# Atari_2600_OD.net
KiCad netlist of a schematic drawn in EAGLE
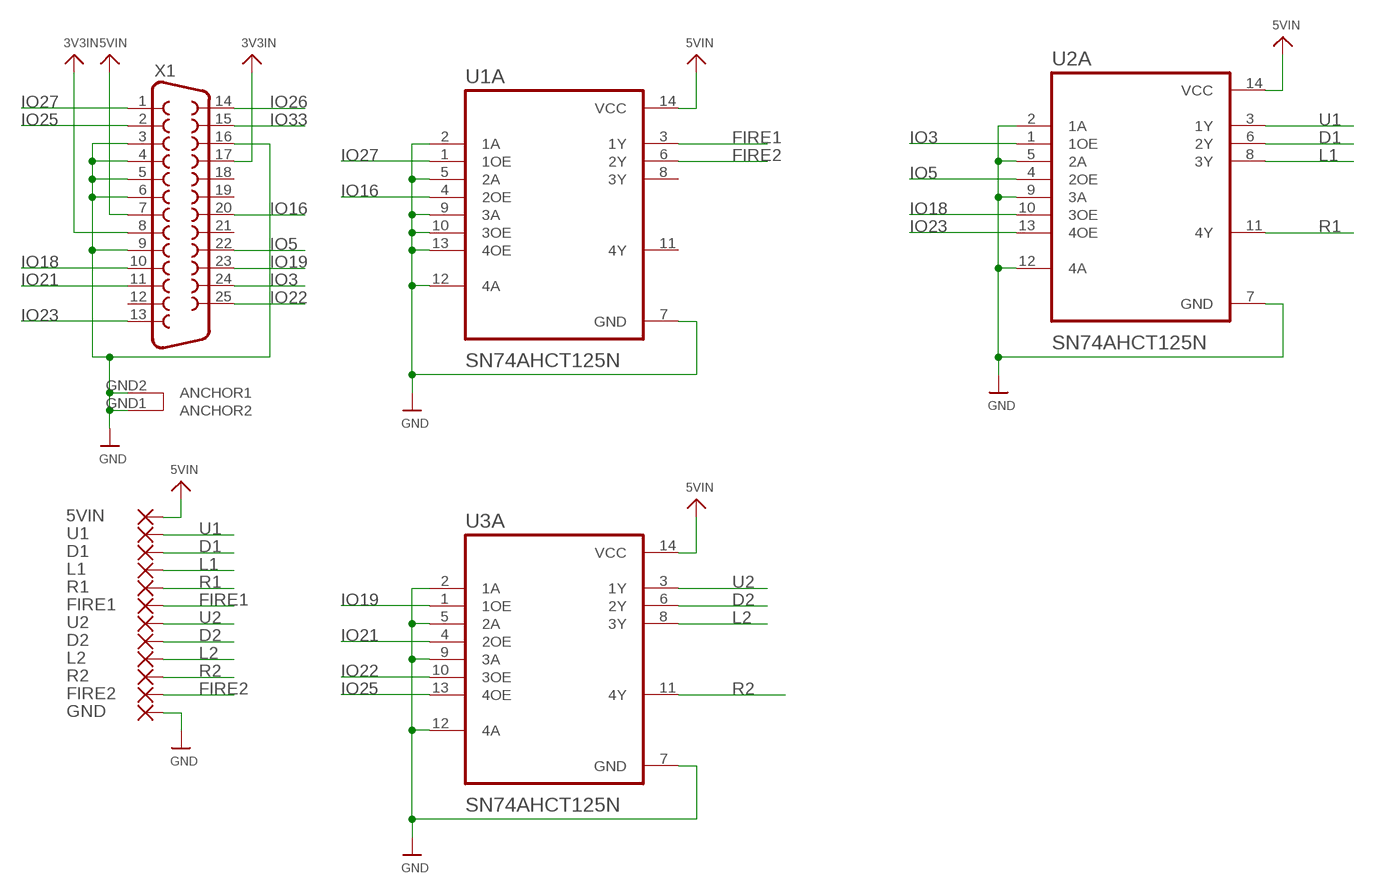
[diagram p0: schematic, sheet 1]

(export (version "E")
  (design (tool "Eeschema 10.0.6"))
  (components
    (comp (ref "5VIN")
      (value "SMD5")
      (footprint "eagle-import:SMD2,54-5,08")
      (libsource (lib "eagle-import") (part "SMD5"))
    )
    (comp (ref "D1")
      (value "SMD5")
      (footprint "eagle-import:SMD2,54-5,08")
      (libsource (lib "eagle-import") (part "SMD5"))
    )
    (comp (ref "D2")
      (value "SMD5")
      (footprint "eagle-import:SMD2,54-5,08")
      (libsource (lib "eagle-import") (part "SMD5"))
    )
    (comp (ref "FIRE1")
      (value "SMD5")
      (footprint "eagle-import:SMD2,54-5,08")
      (libsource (lib "eagle-import") (part "SMD5"))
    )
    (comp (ref "FIRE2")
      (value "SMD5")
      (footprint "eagle-import:SMD2,54-5,08")
      (libsource (lib "eagle-import") (part "SMD5"))
    )
    (comp (ref "GND")
      (value "SMD5")
      (footprint "eagle-import:SMD2,54-5,08")
      (libsource (lib "eagle-import") (part "SMD5"))
    )
    (comp (ref "L1")
      (value "SMD5")
      (footprint "eagle-import:SMD2,54-5,08")
      (libsource (lib "eagle-import") (part "SMD5"))
    )
    (comp (ref "L2")
      (value "SMD5")
      (footprint "eagle-import:SMD2,54-5,08")
      (libsource (lib "eagle-import") (part "SMD5"))
    )
    (comp (ref "R1")
      (value "SMD5")
      (footprint "eagle-import:SMD2,54-5,08")
      (libsource (lib "eagle-import") (part "SMD5"))
    )
    (comp (ref "R2")
      (value "SMD5")
      (footprint "eagle-import:SMD2,54-5,08")
      (libsource (lib "eagle-import") (part "SMD5"))
    )
    (comp (ref "U1")
      (value "SMD5")
      (footprint "eagle-import:SMD2,54-5,08")
      (libsource (lib "eagle-import") (part "SMD5"))
    )
    (comp (ref "U1A")
      (value "SN74AHCT125N")
      (footprint "eagle-import:DIP794W45P254L1969H508Q14")
      (fields (field (name "MF") "Texas Instruments"))
      (libsource (lib "eagle-import") (part "SN74AHCT125N"))
    )
    (comp (ref "U2")
      (value "SMD5")
      (footprint "eagle-import:SMD2,54-5,08")
      (libsource (lib "eagle-import") (part "SMD5"))
    )
    (comp (ref "U2A")
      (value "SN74AHCT125N")
      (footprint "eagle-import:DIP794W45P254L1969H508Q14")
      (fields (field (name "MF") "Texas Instruments"))
      (libsource (lib "eagle-import") (part "SN74AHCT125N"))
    )
    (comp (ref "U3A")
      (value "SN74AHCT125N")
      (footprint "eagle-import:DIP794W45P254L1969H508Q14")
      (fields (field (name "MF") "Texas Instruments"))
      (libsource (lib "eagle-import") (part "SN74AHCT125N"))
    )
    (comp (ref "X1")
      (value "DB25_FEMALEHP")
      (footprint "eagle-import:F25HP")
      (libsource (lib "eagle-import") (part "DB25_FEMALEHP"))
    )
  )
  (nets
    (net (code "1") (name "/D1") (class "Default")
      (node (ref "D1") (pin "1") (pinfunction "P_1") (pintype "passive"))
      (node (ref "U2A") (pin "6") (pinfunction "2Y_6") (pintype "output"))
    )
    (net (code "2") (name "/D2") (class "Default")
      (node (ref "D2") (pin "1") (pinfunction "P_1") (pintype "passive"))
      (node (ref "U3A") (pin "6") (pinfunction "2Y_6") (pintype "output"))
    )
    (net (code "3") (name "/FIRE1") (class "Default")
      (node (ref "FIRE1") (pin "1") (pinfunction "P_1") (pintype "passive"))
      (node (ref "U1A") (pin "3") (pinfunction "1Y_3") (pintype "output"))
    )
    (net (code "4") (name "/FIRE2") (class "Default")
      (node (ref "FIRE2") (pin "1") (pinfunction "P_1") (pintype "passive"))
      (node (ref "U1A") (pin "6") (pinfunction "2Y_6") (pintype "output"))
    )
    (net (code "5") (name "/IO3") (class "Default")
      (node (ref "U2A") (pin "1") (pinfunction "1OE_1") (pintype "input"))
      (node (ref "X1") (pin "24") (pinfunction "24_24") (pintype "passive"))
    )
    (net (code "6") (name "/IO5") (class "Default")
      (node (ref "U2A") (pin "4") (pinfunction "2OE_4") (pintype "input"))
      (node (ref "X1") (pin "22") (pinfunction "22_22") (pintype "passive"))
    )
    (net (code "7") (name "/IO16") (class "Default")
      (node (ref "U1A") (pin "4") (pinfunction "2OE_4") (pintype "input"))
      (node (ref "X1") (pin "20") (pinfunction "20_20") (pintype "passive"))
    )
    (net (code "8") (name "/IO18") (class "Default")
      (node (ref "U2A") (pin "10") (pinfunction "3OE_10") (pintype "input"))
      (node (ref "X1") (pin "10") (pinfunction "10_10") (pintype "passive"))
    )
    (net (code "9") (name "/IO19") (class "Default")
      (node (ref "U3A") (pin "1") (pinfunction "1OE_1") (pintype "input"))
      (node (ref "X1") (pin "23") (pinfunction "23_23") (pintype "passive"))
    )
    (net (code "10") (name "/IO21") (class "Default")
      (node (ref "U3A") (pin "4") (pinfunction "2OE_4") (pintype "input"))
      (node (ref "X1") (pin "11") (pinfunction "11_11") (pintype "passive"))
    )
    (net (code "11") (name "/IO22") (class "Default")
      (node (ref "U3A") (pin "10") (pinfunction "3OE_10") (pintype "input"))
      (node (ref "X1") (pin "25") (pinfunction "25_25") (pintype "passive"))
    )
    (net (code "12") (name "/IO23") (class "Default")
      (node (ref "U2A") (pin "13") (pinfunction "4OE_13") (pintype "input"))
      (node (ref "X1") (pin "13") (pinfunction "13_13") (pintype "passive"))
    )
    (net (code "13") (name "/IO25") (class "Default")
      (node (ref "U3A") (pin "13") (pinfunction "4OE_13") (pintype "input"))
      (node (ref "X1") (pin "2") (pinfunction "2_2") (pintype "passive"))
    )
    (net (code "14") (name "/IO26") (class "Default")
      (node (ref "X1") (pin "14") (pinfunction "14_14") (pintype "passive"))
    )
    (net (code "15") (name "/IO27") (class "Default")
      (node (ref "U1A") (pin "1") (pinfunction "1OE_1") (pintype "input"))
      (node (ref "X1") (pin "1") (pinfunction "1_1") (pintype "passive"))
    )
    (net (code "16") (name "/IO33") (class "Default")
      (node (ref "X1") (pin "15") (pinfunction "15_15") (pintype "passive"))
    )
    (net (code "17") (name "/L1") (class "Default")
      (node (ref "L1") (pin "1") (pinfunction "P_1") (pintype "passive"))
      (node (ref "U2A") (pin "8") (pinfunction "3Y_8") (pintype "output"))
    )
    (net (code "18") (name "/L2") (class "Default")
      (node (ref "L2") (pin "1") (pinfunction "P_1") (pintype "passive"))
      (node (ref "U3A") (pin "8") (pinfunction "3Y_8") (pintype "output"))
    )
    (net (code "19") (name "/R1") (class "Default")
      (node (ref "R1") (pin "1") (pinfunction "P_1") (pintype "passive"))
      (node (ref "U2A") (pin "11") (pinfunction "4Y_11") (pintype "output"))
    )
    (net (code "20") (name "/R2") (class "Default")
      (node (ref "R2") (pin "1") (pinfunction "P_1") (pintype "passive"))
      (node (ref "U3A") (pin "11") (pinfunction "4Y_11") (pintype "output"))
    )
    (net (code "21") (name "/U1") (class "Default")
      (node (ref "U1") (pin "1") (pinfunction "P_1") (pintype "passive"))
      (node (ref "U2A") (pin "3") (pinfunction "1Y_3") (pintype "output"))
    )
    (net (code "22") (name "/U2") (class "Default")
      (node (ref "U2") (pin "1") (pinfunction "P_1") (pintype "passive"))
      (node (ref "U3A") (pin "3") (pinfunction "1Y_3") (pintype "output"))
    )
    (net (code "23") (name "3V3IN") (class "Default")
      (node (ref "X1") (pin "17") (pinfunction "17_17") (pintype "passive"))
      (node (ref "X1") (pin "8") (pinfunction "8_8") (pintype "passive"))
    )
    (net (code "24") (name "5VIN") (class "Default")
      (node (ref "5VIN") (pin "1") (pinfunction "P_1") (pintype "passive"))
      (node (ref "U1A") (pin "14") (pinfunction "VCC_14") (pintype "power_in"))
      (node (ref "U2A") (pin "14") (pinfunction "VCC_14") (pintype "power_in"))
      (node (ref "U3A") (pin "14") (pinfunction "VCC_14") (pintype "power_in"))
      (node (ref "X1") (pin "7") (pinfunction "7_7") (pintype "passive"))
    )
    (net (code "25") (name "GND") (class "Default")
      (node (ref "GND") (pin "1") (pinfunction "P_1") (pintype "passive"))
      (node (ref "U1A") (pin "10") (pinfunction "3OE_10") (pintype "input"))
      (node (ref "U1A") (pin "12") (pinfunction "4A_12") (pintype "bidirectional"))
      (node (ref "U1A") (pin "13") (pinfunction "4OE_13") (pintype "input"))
      (node (ref "U1A") (pin "2") (pinfunction "1A_2") (pintype "input"))
      (node (ref "U1A") (pin "5") (pinfunction "2A_5") (pintype "input"))
      (node (ref "U1A") (pin "7") (pinfunction "GND_7") (pintype "power_in"))
      (node (ref "U1A") (pin "9") (pinfunction "3A_9") (pintype "input"))
      (node (ref "U2A") (pin "12") (pinfunction "4A_12") (pintype "bidirectional"))
      (node (ref "U2A") (pin "2") (pinfunction "1A_2") (pintype "input"))
      (node (ref "U2A") (pin "5") (pinfunction "2A_5") (pintype "input"))
      (node (ref "U2A") (pin "7") (pinfunction "GND_7") (pintype "power_in"))
      (node (ref "U2A") (pin "9") (pinfunction "3A_9") (pintype "input"))
      (node (ref "U3A") (pin "12") (pinfunction "4A_12") (pintype "bidirectional"))
      (node (ref "U3A") (pin "2") (pinfunction "1A_2") (pintype "input"))
      (node (ref "U3A") (pin "5") (pinfunction "2A_5") (pintype "input"))
      (node (ref "U3A") (pin "7") (pinfunction "GND_7") (pintype "power_in"))
      (node (ref "U3A") (pin "9") (pinfunction "3A_9") (pintype "input"))
      (node (ref "X1") (pin "16") (pinfunction "16_16") (pintype "passive"))
      (node (ref "X1") (pin "3") (pinfunction "3_3") (pintype "passive"))
      (node (ref "X1") (pin "4") (pinfunction "4_4") (pintype "passive"))
      (node (ref "X1") (pin "5") (pinfunction "5_5") (pintype "passive"))
      (node (ref "X1") (pin "6") (pinfunction "6_6") (pintype "passive"))
      (node (ref "X1") (pin "9") (pinfunction "9_9") (pintype "passive"))
      (node (ref "X1") (pin "GND1") (pinfunction "ANCHOR2_GND1") (pintype "bidirectional"))
      (node (ref "X1") (pin "GND2") (pinfunction "ANCHOR1_GND2") (pintype "bidirectional"))
    )
    (net (code "26") (name "unconnected-(U1A-3Y-Pad8)") (class "Default")
      (node (ref "U1A") (pin "8") (pinfunction "3Y_8") (pintype "output"))
    )
    (net (code "27") (name "unconnected-(U1A-4Y-Pad11)") (class "Default")
      (node (ref "U1A") (pin "11") (pinfunction "4Y_11") (pintype "output"))
    )
    (net (code "28") (name "unconnected-(X1-Pad12)") (class "Default")
      (node (ref "X1") (pin "12") (pinfunction "12_12") (pintype "passive"))
    )
    (net (code "29") (name "unconnected-(X1-Pad18)") (class "Default")
      (node (ref "X1") (pin "18") (pinfunction "18_18") (pintype "passive"))
    )
    (net (code "30") (name "unconnected-(X1-Pad19)") (class "Default")
      (node (ref "X1") (pin "19") (pinfunction "19_19") (pintype "passive"))
    )
    (net (code "31") (name "unconnected-(X1-Pad21)") (class "Default")
      (node (ref "X1") (pin "21") (pinfunction "21_21") (pintype "passive"))
    )
  )
)
